# 1_panel.net
KiCad netlist of a schematic drawn in Altium Designer
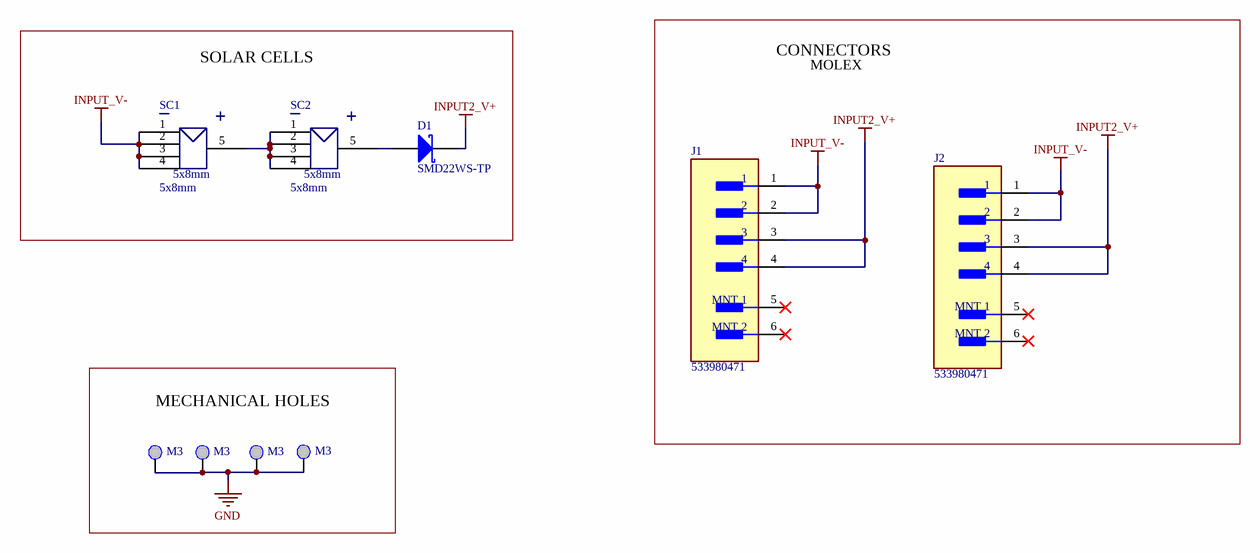
[diagram p0: 1_panel.schdoc]

(export (version "E")
  (design (tool "Eeschema 10.0.6"))
  (components
    (comp (ref "D1")
      (value "SMD22WS-TP")
      (footprint "SOD323F")
      (description "Diode Schottky 20 V 2A Surface Mount SOD-323")
      (libsource (lib "schematics_library_legacy") (part "DIODE_SCHOTTKY_20V_2A_SMD22WS-TP"))
    )
    (comp (ref "J1")
      (value "533980471")
      (footprint "FP-533980471-MFG")
      (description "CONN HEADER SMD 4POS 1.25MM")
      (fields
        (field (name "OCTOPART") "https://octopart.com/53398-0471-molex-655296")
        (field (name "MANUFACTURER") "Molex")
      )
      (libsource (lib "Altium Content Vault") (part "3b6f738a5616415d78381ad43816e4a"))
    )
    (comp (ref "J2")
      (value "533980471")
      (footprint "FP-533980471-MFG")
      (description "CONN HEADER SMD 4POS 1.25MM")
      (fields
        (field (name "OCTOPART") "https://octopart.com/53398-0471-molex-655296")
        (field (name "MANUFACTURER") "Molex")
      )
      (libsource (lib "Altium Content Vault") (part "3b6f738a5616415d78381ad43816e4a"))
    )
    (comp (ref "MEC1")
      (value "M3")
      (footprint "HOLE6x6mm")
      (description "M3 hole")
      (libsource (lib "schematics_library_legacy") (part "M3 hole"))
    )
    (comp (ref "MEC2")
      (value "M3")
      (footprint "HOLE6x6mm")
      (description "M3 hole")
      (libsource (lib "schematics_library_legacy") (part "M3 hole"))
    )
    (comp (ref "MEC3")
      (value "M3")
      (footprint "HOLE6x6mm")
      (description "M3 hole")
      (libsource (lib "schematics_library_legacy") (part "M3 hole"))
    )
    (comp (ref "MEC4")
      (value "M3")
      (footprint "HOLE6x6mm")
      (description "M3 hole")
      (libsource (lib "schematics_library_legacy") (part "M3 hole"))
    )
    (comp (ref "SC1")
      (value "5x8mm")
      (footprint "SOLAR_CELL")
      (fields (field (name "MANUFACTURER") "Yim Space"))
      (libsource (lib "Schlib1") (part "SOLAR CELL"))
    )
    (comp (ref "SC2")
      (value "5x8mm")
      (footprint "SOLAR_CELL")
      (fields (field (name "MANUFACTURER") "Yim Space"))
      (libsource (lib "Schlib1") (part "SOLAR CELL"))
    )
  )
  (nets
    (net (code "1") (name "GND") (class "Default")
      (node (ref "MEC1") (pin "0") (pinfunction "0_0") (pintype "passive"))
      (node (ref "MEC2") (pin "0") (pinfunction "0_0") (pintype "passive"))
      (node (ref "MEC3") (pin "0") (pinfunction "0_0") (pintype "passive"))
      (node (ref "MEC4") (pin "0") (pinfunction "0_0") (pintype "passive"))
    )
    (net (code "2") (name "INPUT2_V+") (class "Default")
      (node (ref "D1") (pin "1") (pinfunction "K_1") (pintype "passive"))
      (node (ref "J1") (pin "3") (pinfunction "3_3") (pintype "passive"))
      (node (ref "J1") (pin "4") (pinfunction "4_4") (pintype "passive"))
      (node (ref "J2") (pin "3") (pinfunction "3_3") (pintype "passive"))
      (node (ref "J2") (pin "4") (pinfunction "4_4") (pintype "passive"))
    )
    (net (code "3") (name "INPUT_V-") (class "Default")
      (node (ref "J1") (pin "1") (pinfunction "1_1") (pintype "passive"))
      (node (ref "J1") (pin "2") (pinfunction "2_2") (pintype "passive"))
      (node (ref "J2") (pin "1") (pinfunction "1_1") (pintype "passive"))
      (node (ref "J2") (pin "2") (pinfunction "2_2") (pintype "passive"))
      (node (ref "SC1") (pin "1") (pinfunction "V+_1") (pintype "power_in"))
      (node (ref "SC1") (pin "2") (pinfunction "V-_2") (pintype "power_in"))
      (node (ref "SC1") (pin "3") (pinfunction "3_3") (pintype "passive"))
      (node (ref "SC1") (pin "4") (pinfunction "4_4") (pintype "passive"))
    )
    (net (code "4") (name "Net-(D1-A)") (class "Default")
      (node (ref "D1") (pin "2") (pinfunction "A_2") (pintype "passive"))
      (node (ref "SC2") (pin "5") (pinfunction "5_5") (pintype "passive"))
    )
    (net (code "5") (name "Net-(SC2-V+)") (class "Default")
      (node (ref "SC1") (pin "5") (pinfunction "5_5") (pintype "passive"))
      (node (ref "SC2") (pin "1") (pinfunction "V+_1") (pintype "power_in"))
      (node (ref "SC2") (pin "2") (pinfunction "V-_2") (pintype "power_in"))
      (node (ref "SC2") (pin "3") (pinfunction "3_3") (pintype "passive"))
      (node (ref "SC2") (pin "4") (pinfunction "4_4") (pintype "passive"))
    )
    (net (code "6") (name "unconnected-(J1-MNT_1-Pad5)") (class "Default")
      (node (ref "J1") (pin "5") (pinfunction "MNT_1_5") (pintype "passive+no_connect"))
    )
    (net (code "7") (name "unconnected-(J1-MNT_2-Pad6)") (class "Default")
      (node (ref "J1") (pin "6") (pinfunction "MNT_2_6") (pintype "passive+no_connect"))
    )
    (net (code "8") (name "unconnected-(J2-MNT_1-Pad5)") (class "Default")
      (node (ref "J2") (pin "5") (pinfunction "MNT_1_5") (pintype "passive+no_connect"))
    )
    (net (code "9") (name "unconnected-(J2-MNT_2-Pad6)") (class "Default")
      (node (ref "J2") (pin "6") (pinfunction "MNT_2_6") (pintype "passive+no_connect"))
    )
  )
)
